# main.net
KiCad netlist of a schematic drawn in EAGLE
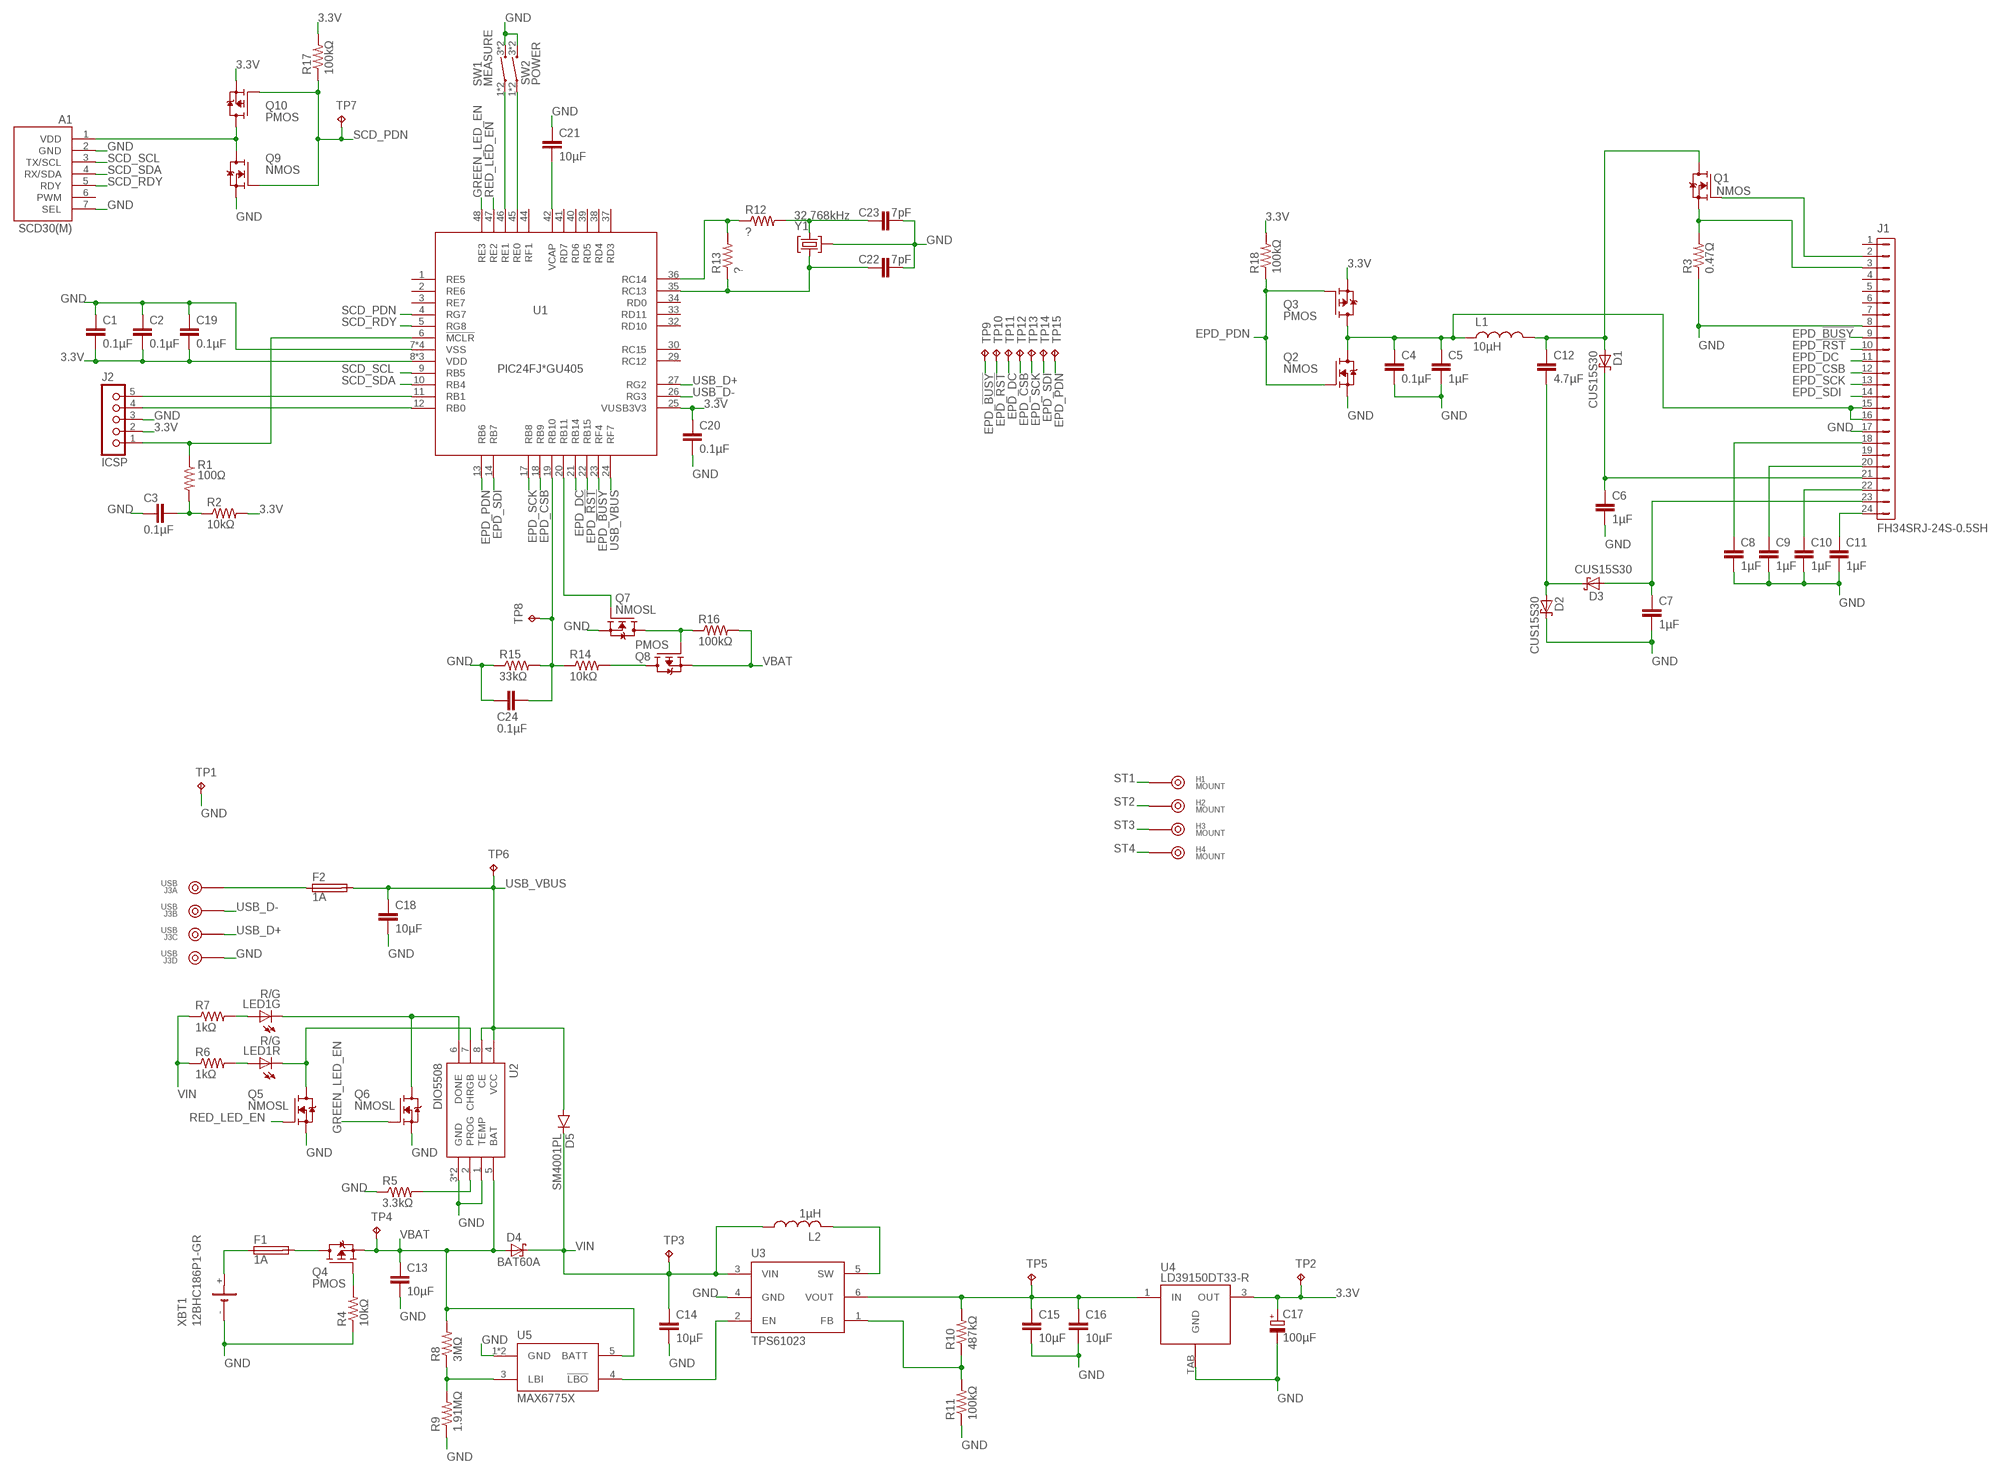
[diagram p0: schematic, sheet 1]

(export (version "E")
  (design (tool "Eeschema 10.0.6"))
  (components
    (comp (ref "A1")
      (value "SCD30(M)")
      (footprint "eagle-import:SCD30-MIRRORED")
      (libsource (lib "eagle-import") (part "SCD30(M)"))
    )
    (comp (ref "C1")
      (value "0.1µF")
      (footprint "eagle-import:C0603")
      (libsource (lib "eagle-import") (part "C-EUC0603"))
    )
    (comp (ref "C2")
      (value "0.1µF")
      (footprint "eagle-import:C0603")
      (libsource (lib "eagle-import") (part "C-EUC0603"))
    )
    (comp (ref "C3")
      (value "0.1µF")
      (footprint "eagle-import:C0603")
      (libsource (lib "eagle-import") (part "C-EUC0603"))
    )
    (comp (ref "C4")
      (value "0.1µF")
      (footprint "eagle-import:C0603")
      (libsource (lib "eagle-import") (part "C-EUC0603"))
    )
    (comp (ref "C5")
      (value "1µF")
      (footprint "eagle-import:C0603")
      (libsource (lib "eagle-import") (part "C-EUC0603"))
    )
    (comp (ref "C6")
      (value "1µF")
      (footprint "eagle-import:C0603")
      (libsource (lib "eagle-import") (part "C-EUC0603"))
    )
    (comp (ref "C7")
      (value "1µF")
      (footprint "eagle-import:C0603")
      (libsource (lib "eagle-import") (part "C-EUC0603"))
    )
    (comp (ref "C8")
      (value "1µF")
      (footprint "eagle-import:C0603")
      (libsource (lib "eagle-import") (part "C-EUC0603"))
    )
    (comp (ref "C9")
      (value "1µF")
      (footprint "eagle-import:C0603")
      (libsource (lib "eagle-import") (part "C-EUC0603"))
    )
    (comp (ref "C10")
      (value "1µF")
      (footprint "eagle-import:C0603")
      (libsource (lib "eagle-import") (part "C-EUC0603"))
    )
    (comp (ref "C11")
      (value "1µF")
      (footprint "eagle-import:C0603")
      (libsource (lib "eagle-import") (part "C-EUC0603"))
    )
    (comp (ref "C12")
      (value "4.7µF")
      (footprint "eagle-import:C0805")
      (libsource (lib "eagle-import") (part "C-EUC0805"))
    )
    (comp (ref "C13")
      (value "10µF")
      (footprint "eagle-import:C0805")
      (libsource (lib "eagle-import") (part "C-EUC0805"))
    )
    (comp (ref "C14")
      (value "10µF")
      (footprint "eagle-import:C0805")
      (libsource (lib "eagle-import") (part "C-EUC0805"))
    )
    (comp (ref "C15")
      (value "10µF")
      (footprint "eagle-import:C0805")
      (libsource (lib "eagle-import") (part "C-EUC0805"))
    )
    (comp (ref "C16")
      (value "10µF")
      (footprint "eagle-import:C0805")
      (libsource (lib "eagle-import") (part "C-EUC0805"))
    )
    (comp (ref "C17")
      (value "100µF")
      (footprint "eagle-import:PANASONIC_D")
      (libsource (lib "eagle-import") (part "CPOL-EUD"))
    )
    (comp (ref "C18")
      (value "10µF")
      (footprint "eagle-import:C0805")
      (libsource (lib "eagle-import") (part "C-EUC0805"))
    )
    (comp (ref "C19")
      (value "0.1µF")
      (footprint "eagle-import:C0603")
      (libsource (lib "eagle-import") (part "C-EUC0603"))
    )
    (comp (ref "C20")
      (value "0.1µF")
      (footprint "eagle-import:C0603")
      (libsource (lib "eagle-import") (part "C-EUC0603"))
    )
    (comp (ref "C21")
      (value "10µF")
      (footprint "eagle-import:C0805")
      (libsource (lib "eagle-import") (part "C-EUC0805"))
    )
    (comp (ref "C22")
      (value "7pF")
      (footprint "eagle-import:C0603")
      (libsource (lib "eagle-import") (part "C-EUC0603"))
    )
    (comp (ref "C23")
      (value "7pF")
      (footprint "eagle-import:C0603")
      (libsource (lib "eagle-import") (part "C-EUC0603"))
    )
    (comp (ref "C24")
      (value "0.1µF")
      (footprint "eagle-import:C0603")
      (libsource (lib "eagle-import") (part "C-EUC0603"))
    )
    (comp (ref "D1")
      (value "CUS15S30")
      (footprint "eagle-import:SOD323")
      (libsource (lib "eagle-import") (part "SOD323-SCHOTTKY"))
    )
    (comp (ref "D2")
      (value "CUS15S30")
      (footprint "eagle-import:SOD323")
      (libsource (lib "eagle-import") (part "SOD323-SCHOTTKY"))
    )
    (comp (ref "D3")
      (value "CUS15S30")
      (footprint "eagle-import:SOD323")
      (libsource (lib "eagle-import") (part "SOD323-SCHOTTKY"))
    )
    (comp (ref "D4")
      (value "BAT60A")
      (footprint "eagle-import:SOD323")
      (libsource (lib "eagle-import") (part "ExtraParts_SOD323-SCHOTTKY"))
    )
    (comp (ref "D5")
      (value "SM4001PL")
      (footprint "eagle-import:SOD123")
      (libsource (lib "eagle-import") (part "DIODE-SOD123"))
    )
    (comp (ref "F1")
      (value "1A")
      (footprint "eagle-import:C0603")
      (libsource (lib "eagle-import") (part "0603-FUSE"))
    )
    (comp (ref "F2")
      (value "1A")
      (footprint "eagle-import:C0603")
      (libsource (lib "eagle-import") (part "0603-FUSE"))
    )
    (comp (ref "H1")
      (value "MOUNT")
      (footprint "eagle-import:7466313R")
      (libsource (lib "eagle-import") (part "7466313R"))
    )
    (comp (ref "H2")
      (value "MOUNT")
      (footprint "eagle-import:7466313R")
      (libsource (lib "eagle-import") (part "7466313R"))
    )
    (comp (ref "H3")
      (value "MOUNT")
      (footprint "eagle-import:7466313R")
      (libsource (lib "eagle-import") (part "7466313R"))
    )
    (comp (ref "H4")
      (value "MOUNT")
      (footprint "eagle-import:7466313R")
      (libsource (lib "eagle-import") (part "7466313R"))
    )
    (comp (ref "J1")
      (value "FH34SRJ-24S-0.5SH")
      (footprint "eagle-import:FH34SRJ-24S-0.5SH")
      (libsource (lib "eagle-import") (part "FH34SRJ-24S-0.5SH"))
    )
    (comp (ref "J2")
      (value "ICSP")
      (footprint "eagle-import:5PIN-1.27")
      (libsource (lib "eagle-import") (part "5PIN-1.27"))
    )
    (comp (ref "J3")
      (value "USB")
      (footprint "eagle-import:4PIN")
      (libsource (lib "eagle-import") (part "GEN-4PIN"))
    )
    (comp (ref "L1")
      (value "10µH")
      (footprint "eagle-import:L3225M")
      (libsource (lib "eagle-import") (part "L-USL3225M"))
    )
    (comp (ref "L2")
      (value "1µH")
      (footprint "eagle-import:TYS4030")
      (libsource (lib "eagle-import") (part "TYS4030"))
    )
    (comp (ref "LED1")
      (value "R/G")
      (footprint "eagle-import:0805-DUALLED")
      (libsource (lib "eagle-import") (part "APHBM2012LSURKZGKC"))
    )
    (comp (ref "Q1")
      (value "NMOS")
      (footprint "eagle-import:SOT23")
      (libsource (lib "eagle-import") (part "SOT23-N-MOSFET"))
    )
    (comp (ref "Q2")
      (value "NMOS")
      (footprint "eagle-import:SOT23")
      (libsource (lib "eagle-import") (part "SOT23-N-MOSFET"))
    )
    (comp (ref "Q3")
      (value "PMOS")
      (footprint "eagle-import:SOT23")
      (libsource (lib "eagle-import") (part "SOT23-P-MOSFET"))
    )
    (comp (ref "Q4")
      (value "PMOS")
      (footprint "eagle-import:SOT23")
      (libsource (lib "eagle-import") (part "SOT23-P-MOSFET"))
    )
    (comp (ref "Q5")
      (value "NMOSL")
      (footprint "eagle-import:SOT23")
      (libsource (lib "eagle-import") (part "SOT23-N-MOSFET"))
    )
    (comp (ref "Q6")
      (value "NMOSL")
      (footprint "eagle-import:SOT23")
      (libsource (lib "eagle-import") (part "SOT23-N-MOSFET"))
    )
    (comp (ref "Q7")
      (value "NMOSL")
      (footprint "eagle-import:SOT23")
      (libsource (lib "eagle-import") (part "SOT23-N-MOSFET"))
    )
    (comp (ref "Q8")
      (value "PMOS")
      (footprint "eagle-import:SOT23")
      (libsource (lib "eagle-import") (part "SOT23-P-MOSFET"))
    )
    (comp (ref "Q9")
      (value "NMOS")
      (footprint "eagle-import:SOT23")
      (libsource (lib "eagle-import") (part "SOT23-N-MOSFET"))
    )
    (comp (ref "Q10")
      (value "PMOS")
      (footprint "eagle-import:SOT23")
      (libsource (lib "eagle-import") (part "SOT23-P-MOSFET"))
    )
    (comp (ref "R1")
      (value "100Ω")
      (footprint "eagle-import:R0603")
      (libsource (lib "eagle-import") (part "R-US_R0603"))
    )
    (comp (ref "R2")
      (value "10kΩ")
      (footprint "eagle-import:R0603")
      (libsource (lib "eagle-import") (part "R-US_R0603"))
    )
    (comp (ref "R3")
      (value "0.47Ω")
      (footprint "eagle-import:R0603")
      (libsource (lib "eagle-import") (part "R-US_R0603"))
    )
    (comp (ref "R4")
      (value "10kΩ")
      (footprint "eagle-import:R0603")
      (libsource (lib "eagle-import") (part "R-US_R0603"))
    )
    (comp (ref "R5")
      (value "3.3kΩ")
      (footprint "eagle-import:R0603")
      (libsource (lib "eagle-import") (part "R-US_R0603"))
    )
    (comp (ref "R6")
      (value "1kΩ")
      (footprint "eagle-import:R0603")
      (libsource (lib "eagle-import") (part "R-US_R0603"))
    )
    (comp (ref "R7")
      (value "1kΩ")
      (footprint "eagle-import:R0603")
      (libsource (lib "eagle-import") (part "R-US_R0603"))
    )
    (comp (ref "R8")
      (value "3MΩ")
      (footprint "eagle-import:R0603")
      (libsource (lib "eagle-import") (part "R-US_R0603"))
    )
    (comp (ref "R9")
      (value "1.91MΩ")
      (footprint "eagle-import:R0603")
      (libsource (lib "eagle-import") (part "R-US_R0603"))
    )
    (comp (ref "R10")
      (value "487kΩ")
      (footprint "eagle-import:R0603")
      (libsource (lib "eagle-import") (part "R-US_R0603"))
    )
    (comp (ref "R11")
      (value "100kΩ")
      (footprint "eagle-import:R0603")
      (libsource (lib "eagle-import") (part "R-US_R0603"))
    )
    (comp (ref "R12")
      (value "?")
      (footprint "eagle-import:R0603")
      (libsource (lib "eagle-import") (part "R-US_R0603"))
    )
    (comp (ref "R13")
      (value "?")
      (footprint "eagle-import:R0603")
      (libsource (lib "eagle-import") (part "R-US_R0603"))
    )
    (comp (ref "R14")
      (value "10kΩ")
      (footprint "eagle-import:R0603")
      (libsource (lib "eagle-import") (part "R-US_R0603"))
    )
    (comp (ref "R15")
      (value "33kΩ")
      (footprint "eagle-import:R0603")
      (libsource (lib "eagle-import") (part "R-US_R0603"))
    )
    (comp (ref "R16")
      (value "100kΩ")
      (footprint "eagle-import:R0603")
      (libsource (lib "eagle-import") (part "R-US_R0603"))
    )
    (comp (ref "R17")
      (value "100kΩ")
      (footprint "eagle-import:R0603")
      (libsource (lib "eagle-import") (part "R-US_R0603"))
    )
    (comp (ref "R18")
      (value "100kΩ")
      (footprint "eagle-import:R0603")
      (libsource (lib "eagle-import") (part "R-US_R0603"))
    )
    (comp (ref "SW1")
      (value "MEASURE")
      (footprint "eagle-import:PTS647")
      (libsource (lib "eagle-import") (part "PTS647"))
    )
    (comp (ref "SW2")
      (value "POWER")
      (footprint "eagle-import:PTS647")
      (libsource (lib "eagle-import") (part "PTS647"))
    )
    (comp (ref "TP1")
      (value "RCU-0(J)")
      (footprint "eagle-import:TP_0603_JOINED")
      (fields (field (name "TP_SIGNAL_NAME") "GND"))
      (libsource (lib "eagle-import") (part "RCU-0(J)"))
    )
    (comp (ref "TP2")
      (value "RCU-0(J)")
      (footprint "eagle-import:TP_0603_JOINED")
      (fields (field (name "TP_SIGNAL_NAME") "3.3V"))
      (libsource (lib "eagle-import") (part "RCU-0(J)"))
    )
    (comp (ref "TP3")
      (value "RCU-0(J)")
      (footprint "eagle-import:TP_0603_JOINED")
      (fields (field (name "TP_SIGNAL_NAME") "VIN"))
      (libsource (lib "eagle-import") (part "RCU-0(J)"))
    )
    (comp (ref "TP4")
      (value "RCU-0(J)")
      (footprint "eagle-import:TP_0603_JOINED")
      (fields (field (name "TP_SIGNAL_NAME") "VBAT"))
      (libsource (lib "eagle-import") (part "RCU-0(J)"))
    )
    (comp (ref "TP5")
      (value "RCU-0(J)")
      (footprint "eagle-import:TP_0603_JOINED")
      (fields (field (name "TP_SIGNAL_NAME") "VBOOST"))
      (libsource (lib "eagle-import") (part "RCU-0(J)"))
    )
    (comp (ref "TP6")
      (value "RCU-0(J)")
      (footprint "eagle-import:TP_0603_JOINED")
      (fields (field (name "TP_SIGNAL_NAME") "USB_V"))
      (libsource (lib "eagle-import") (part "RCU-0(J)"))
    )
    (comp (ref "TP7")
      (value "RCU-0(J)")
      (footprint "eagle-import:TP_0603_JOINED")
      (fields (field (name "TP_SIGNAL_NAME") "SCD_PDN"))
      (libsource (lib "eagle-import") (part "RCU-0(J)"))
    )
    (comp (ref "TP8")
      (value "RCU-0(J)")
      (footprint "eagle-import:TP_0603_JOINED")
      (fields (field (name "TP_SIGNAL_NAME") "VBAT_M"))
      (libsource (lib "eagle-import") (part "RCU-0(J)"))
    )
    (comp (ref "TP9")
      (value "RCU-0(J)")
      (footprint "eagle-import:TP_0603_JOINED")
      (fields (field (name "TP_SIGNAL_NAME") "EPD_!BUSY"))
      (libsource (lib "eagle-import") (part "RCU-0(J)"))
    )
    (comp (ref "TP10")
      (value "RCU-0(J)")
      (footprint "eagle-import:TP_0603_JOINED")
      (fields (field (name "TP_SIGNAL_NAME") "EPD_!RST"))
      (libsource (lib "eagle-import") (part "RCU-0(J)"))
    )
    (comp (ref "TP11")
      (value "RCU-0(J)")
      (footprint "eagle-import:TP_0603_JOINED")
      (fields (field (name "TP_SIGNAL_NAME") "EPD_DC"))
      (libsource (lib "eagle-import") (part "RCU-0(J)"))
    )
    (comp (ref "TP12")
      (value "RCU-0(J)")
      (footprint "eagle-import:TP_0603_JOINED")
      (fields (field (name "TP_SIGNAL_NAME") "EPD_CSB"))
      (libsource (lib "eagle-import") (part "RCU-0(J)"))
    )
    (comp (ref "TP13")
      (value "RCU-0(J)")
      (footprint "eagle-import:TP_0603_JOINED")
      (fields (field (name "TP_SIGNAL_NAME") "EPD_SCK"))
      (libsource (lib "eagle-import") (part "RCU-0(J)"))
    )
    (comp (ref "TP14")
      (value "RCU-0(J)")
      (footprint "eagle-import:TP_0603_JOINED")
      (fields (field (name "TP_SIGNAL_NAME") "EPD_SDI"))
      (libsource (lib "eagle-import") (part "RCU-0(J)"))
    )
    (comp (ref "TP15")
      (value "RCU-0(J)")
      (footprint "eagle-import:TP_0603_JOINED")
      (fields (field (name "TP_SIGNAL_NAME") "EPD_PDN"))
      (libsource (lib "eagle-import") (part "RCU-0(J)"))
    )
    (comp (ref "U1")
      (value "PIC24FJ*GU405")
      (footprint "eagle-import:TQFP48")
      (libsource (lib "eagle-import") (part "PIC24FJGU405"))
    )
    (comp (ref "U2")
      (value "DIO5508")
      (footprint "eagle-import:SOIC8-EP")
      (libsource (lib "eagle-import") (part "DIO5508"))
    )
    (comp (ref "U3")
      (value "TPS61023")
      (footprint "eagle-import:SOT563")
      (libsource (lib "eagle-import") (part "TPS61023"))
    )
    (comp (ref "U4")
      (value "LD39150DT33-R")
      (footprint "eagle-import:DPAK")
      (libsource (lib "eagle-import") (part "DPAK-LDO"))
    )
    (comp (ref "U5")
      (value "MAX6775X")
      (footprint "eagle-import:SC70-5")
      (libsource (lib "eagle-import") (part "MAX6776X"))
    )
    (comp (ref "XBT1")
      (value "12BHC186P1-GR")
      (footprint "eagle-import:12BHC186P1-GR")
      (libsource (lib "eagle-import") (part "12BHC186P1-GR"))
    )
    (comp (ref "Y1")
      (value "32.768kHz")
      (footprint "eagle-import:MS1V-T1K")
      (libsource (lib "eagle-import") (part "MS1V-T1K"))
    )
  )
  (nets
    (net (code "1") (name "/3.3V") (class "Default")
      (node (ref "C1") (pin "2") (pinfunction "2_2") (pintype "passive"))
      (node (ref "C17") (pin "+") (pinfunction "+_+") (pintype "passive"))
      (node (ref "C19") (pin "2") (pinfunction "2_2") (pintype "passive"))
      (node (ref "C2") (pin "2") (pinfunction "2_2") (pintype "passive"))
      (node (ref "C20") (pin "1") (pinfunction "1_1") (pintype "passive"))
      (node (ref "J2") (pin "2") (pinfunction "2_2") (pintype "passive"))
      (node (ref "Q10") (pin "2") (pinfunction "S_2") (pintype "passive"))
      (node (ref "Q3") (pin "2") (pinfunction "S_2") (pintype "passive"))
      (node (ref "R17") (pin "2") (pinfunction "2_2") (pintype "passive"))
      (node (ref "R18") (pin "2") (pinfunction "2_2") (pintype "passive"))
      (node (ref "R2") (pin "2") (pinfunction "2_2") (pintype "passive"))
      (node (ref "TP2") (pin "1") (pinfunction "TP_1") (pintype "input"))
      (node (ref "U1") (pin "15") (pinfunction "VDD_15") (pintype "bidirectional"))
      (node (ref "U1") (pin "25") (pinfunction "VUSB3V3_25") (pintype "bidirectional"))
      (node (ref "U1") (pin "28") (pinfunction "VDD_28") (pintype "bidirectional"))
      (node (ref "U1") (pin "8") (pinfunction "VDD_8") (pintype "bidirectional"))
      (node (ref "U4") (pin "3") (pinfunction "OUT_3") (pintype "bidirectional"))
    )
    (net (code "2") (name "/EPD_CSB") (class "Default")
      (node (ref "J1") (pin "12") (pinfunction "12_12") (pintype "passive"))
      (node (ref "TP12") (pin "1") (pinfunction "TP_1") (pintype "input"))
      (node (ref "U1") (pin "18") (pinfunction "RB9_18") (pintype "bidirectional"))
    )
    (net (code "3") (name "/EPD_DC") (class "Default")
      (node (ref "J1") (pin "11") (pinfunction "11_11") (pintype "passive"))
      (node (ref "TP11") (pin "1") (pinfunction "TP_1") (pintype "input"))
      (node (ref "U1") (pin "21") (pinfunction "RB14_21") (pintype "bidirectional"))
    )
    (net (code "4") (name "/EPD_PDN") (class "Default")
      (node (ref "Q2") (pin "1") (pinfunction "G_1") (pintype "passive"))
      (node (ref "Q3") (pin "1") (pinfunction "G_1") (pintype "passive"))
      (node (ref "R18") (pin "1") (pinfunction "1_1") (pintype "passive"))
      (node (ref "TP15") (pin "1") (pinfunction "TP_1") (pintype "input"))
      (node (ref "U1") (pin "13") (pinfunction "RB6_13") (pintype "bidirectional"))
    )
    (net (code "5") (name "/EPD_SCK") (class "Default")
      (node (ref "J1") (pin "13") (pinfunction "13_13") (pintype "passive"))
      (node (ref "TP13") (pin "1") (pinfunction "TP_1") (pintype "input"))
      (node (ref "U1") (pin "17") (pinfunction "RB8_17") (pintype "bidirectional"))
    )
    (net (code "6") (name "/EPD_SDI") (class "Default")
      (node (ref "J1") (pin "14") (pinfunction "14_14") (pintype "passive"))
      (node (ref "TP14") (pin "1") (pinfunction "TP_1") (pintype "input"))
      (node (ref "U1") (pin "14") (pinfunction "RB7_14") (pintype "bidirectional"))
    )
    (net (code "7") (name "/EPD_~{BUSY}") (class "Default")
      (node (ref "J1") (pin "9") (pinfunction "9_9") (pintype "passive"))
      (node (ref "TP9") (pin "1") (pinfunction "TP_1") (pintype "input"))
      (node (ref "U1") (pin "23") (pinfunction "RF4_23") (pintype "bidirectional"))
    )
    (net (code "8") (name "/EPD_~{RST}") (class "Default")
      (node (ref "J1") (pin "10") (pinfunction "10_10") (pintype "passive"))
      (node (ref "TP10") (pin "1") (pinfunction "TP_1") (pintype "input"))
      (node (ref "U1") (pin "22") (pinfunction "RB15_22") (pintype "bidirectional"))
    )
    (net (code "9") (name "/GND") (class "Default")
      (node (ref "A1") (pin "2") (pinfunction "GND_2") (pintype "bidirectional"))
      (node (ref "A1") (pin "7") (pinfunction "SEL_7") (pintype "bidirectional"))
      (node (ref "C1") (pin "1") (pinfunction "1_1") (pintype "passive"))
      (node (ref "C10") (pin "2") (pinfunction "2_2") (pintype "passive"))
      (node (ref "C11") (pin "2") (pinfunction "2_2") (pintype "passive"))
      (node (ref "C13") (pin "2") (pinfunction "2_2") (pintype "passive"))
      (node (ref "C14") (pin "2") (pinfunction "2_2") (pintype "passive"))
      (node (ref "C15") (pin "2") (pinfunction "2_2") (pintype "passive"))
      (node (ref "C16") (pin "2") (pinfunction "2_2") (pintype "passive"))
      (node (ref "C17") (pin "-") (pinfunction "-_-") (pintype "passive"))
      (node (ref "C18") (pin "2") (pinfunction "2_2") (pintype "passive"))
      (node (ref "C19") (pin "1") (pinfunction "1_1") (pintype "passive"))
      (node (ref "C2") (pin "1") (pinfunction "1_1") (pintype "passive"))
      (node (ref "C20") (pin "2") (pinfunction "2_2") (pintype "passive"))
      (node (ref "C21") (pin "1") (pinfunction "1_1") (pintype "passive"))
      (node (ref "C22") (pin "2") (pinfunction "2_2") (pintype "passive"))
      (node (ref "C23") (pin "2") (pinfunction "2_2") (pintype "passive"))
      (node (ref "C24") (pin "2") (pinfunction "2_2") (pintype "passive"))
      (node (ref "C3") (pin "2") (pinfunction "2_2") (pintype "passive"))
      (node (ref "C4") (pin "2") (pinfunction "2_2") (pintype "passive"))
      (node (ref "C5") (pin "2") (pinfunction "2_2") (pintype "passive"))
      (node (ref "C6") (pin "2") (pinfunction "2_2") (pintype "passive"))
      (node (ref "C7") (pin "2") (pinfunction "2_2") (pintype "passive"))
      (node (ref "C8") (pin "2") (pinfunction "2_2") (pintype "passive"))
      (node (ref "C9") (pin "2") (pinfunction "2_2") (pintype "passive"))
      (node (ref "D2") (pin "1") (pinfunction "C_1") (pintype "passive"))
      (node (ref "J1") (pin "17") (pinfunction "17_17") (pintype "passive"))
      (node (ref "J1") (pin "8") (pinfunction "8_8") (pintype "passive"))
      (node (ref "J2") (pin "3") (pinfunction "3_3") (pintype "passive"))
      (node (ref "J3") (pin "4") (pinfunction "P$1_4") (pintype "bidirectional"))
      (node (ref "Q2") (pin "2") (pinfunction "S_2") (pintype "passive"))
      (node (ref "Q5") (pin "2") (pinfunction "S_2") (pintype "passive"))
      (node (ref "Q6") (pin "2") (pinfunction "S_2") (pintype "passive"))
      (node (ref "Q7") (pin "2") (pinfunction "S_2") (pintype "passive"))
      (node (ref "Q9") (pin "2") (pinfunction "S_2") (pintype "passive"))
      (node (ref "R11") (pin "1") (pinfunction "1_1") (pintype "passive"))
      (node (ref "R15") (pin "1") (pinfunction "1_1") (pintype "passive"))
      (node (ref "R3") (pin "1") (pinfunction "1_1") (pintype "passive"))
      (node (ref "R4") (pin "1") (pinfunction "1_1") (pintype "passive"))
      (node (ref "R5") (pin "1") (pinfunction "1_1") (pintype "passive"))
      (node (ref "R9") (pin "1") (pinfunction "1_1") (pintype "passive"))
      (node (ref "SW1") (pin "3") (pinfunction "2_3") (pintype "passive"))
      (node (ref "SW1") (pin "4") (pinfunction "2_4") (pintype "passive"))
      (node (ref "SW2") (pin "3") (pinfunction "2_3") (pintype "passive"))
      (node (ref "SW2") (pin "4") (pinfunction "2_4") (pintype "passive"))
      (node (ref "TP1") (pin "1") (pinfunction "TP_1") (pintype "input"))
      (node (ref "U1") (pin "16") (pinfunction "VSS_16") (pintype "bidirectional"))
      (node (ref "U1") (pin "31") (pinfunction "VSS_31") (pintype "bidirectional"))
      (node (ref "U1") (pin "43") (pinfunction "VSS_43") (pintype "bidirectional"))
      (node (ref "U1") (pin "7") (pinfunction "VSS_7") (pintype "bidirectional"))
      (node (ref "U2") (pin "1") (pinfunction "TEMP_1") (pintype "bidirectional"))
      (node (ref "U2") (pin "3") (pinfunction "GND_3") (pintype "bidirectional"))
      (node (ref "U2") (pin "EP") (pinfunction "GND_EP") (pintype "bidirectional"))
      (node (ref "U3") (pin "4") (pinfunction "GND_4") (pintype "bidirectional"))
      (node (ref "U4") (pin "TAB") (pinfunction "GND_TAB") (pintype "bidirectional"))
      (node (ref "U5") (pin "1") (pinfunction "GND_1") (pintype "power_in"))
      (node (ref "U5") (pin "2") (pinfunction "GND_2") (pintype "power_in"))
      (node (ref "XBT1") (pin "-") (pinfunction "-_-") (pintype "passive"))
      (node (ref "Y1") (pin "GND") (pinfunction "3_GND") (pintype "passive"))
    )
    (net (code "10") (name "/GREEN_LED_EN") (class "Default")
      (node (ref "Q6") (pin "1") (pinfunction "G_1") (pintype "passive"))
      (node (ref "U1") (pin "48") (pinfunction "RE3_48") (pintype "bidirectional"))
    )
    (net (code "11") (name "/RED_LED_EN") (class "Default")
      (node (ref "Q5") (pin "1") (pinfunction "G_1") (pintype "passive"))
      (node (ref "U1") (pin "47") (pinfunction "RE2_47") (pintype "bidirectional"))
    )
    (net (code "12") (name "/SCD_PDN") (class "Default")
      (node (ref "Q10") (pin "1") (pinfunction "G_1") (pintype "passive"))
      (node (ref "Q9") (pin "1") (pinfunction "G_1") (pintype "passive"))
      (node (ref "R17") (pin "1") (pinfunction "1_1") (pintype "passive"))
      (node (ref "TP7") (pin "1") (pinfunction "TP_1") (pintype "input"))
      (node (ref "U1") (pin "4") (pinfunction "RG7_4") (pintype "bidirectional"))
    )
    (net (code "13") (name "/SCD_RDY") (class "Default")
      (node (ref "A1") (pin "5") (pinfunction "RDY_5") (pintype "bidirectional"))
      (node (ref "U1") (pin "5") (pinfunction "RG8_5") (pintype "bidirectional"))
    )
    (net (code "14") (name "/SCD_SCL") (class "Default")
      (node (ref "A1") (pin "3") (pinfunction "TX/SCL_3") (pintype "bidirectional"))
      (node (ref "U1") (pin "9") (pinfunction "RB5_9") (pintype "bidirectional"))
    )
    (net (code "15") (name "/SCD_SDA") (class "Default")
      (node (ref "A1") (pin "4") (pinfunction "RX/SDA_4") (pintype "bidirectional"))
      (node (ref "U1") (pin "10") (pinfunction "RB4_10") (pintype "bidirectional"))
    )
    (net (code "16") (name "/ST1") (class "Default")
      (node (ref "H1") (pin "H1") (pinfunction "P$1_H1") (pintype "bidirectional"))
      (node (ref "H1") (pin "H2") (pinfunction "P$1_H2") (pintype "bidirectional"))
      (node (ref "H1") (pin "P") (pinfunction "P$1_P") (pintype "bidirectional"))
    )
    (net (code "17") (name "/ST2") (class "Default")
      (node (ref "H2") (pin "H1") (pinfunction "P$1_H1") (pintype "bidirectional"))
      (node (ref "H2") (pin "H2") (pinfunction "P$1_H2") (pintype "bidirectional"))
      (node (ref "H2") (pin "P") (pinfunction "P$1_P") (pintype "bidirectional"))
    )
    (net (code "18") (name "/ST3") (class "Default")
      (node (ref "H3") (pin "H1") (pinfunction "P$1_H1") (pintype "bidirectional"))
      (node (ref "H3") (pin "H2") (pinfunction "P$1_H2") (pintype "bidirectional"))
      (node (ref "H3") (pin "P") (pinfunction "P$1_P") (pintype "bidirectional"))
    )
    (net (code "19") (name "/ST4") (class "Default")
      (node (ref "H4") (pin "H1") (pinfunction "P$1_H1") (pintype "bidirectional"))
      (node (ref "H4") (pin "H2") (pinfunction "P$1_H2") (pintype "bidirectional"))
      (node (ref "H4") (pin "P") (pinfunction "P$1_P") (pintype "bidirectional"))
    )
    (net (code "20") (name "/USB_D+") (class "Default")
      (node (ref "J3") (pin "3") (pinfunction "P$1_3") (pintype "bidirectional"))
      (node (ref "U1") (pin "27") (pinfunction "RG2_27") (pintype "bidirectional"))
    )
    (net (code "21") (name "/USB_D-") (class "Default")
      (node (ref "J3") (pin "2") (pinfunction "P$1_2") (pintype "bidirectional"))
      (node (ref "U1") (pin "26") (pinfunction "RG3_26") (pintype "bidirectional"))
    )
    (net (code "22") (name "/USB_VBUS") (class "Default")
      (node (ref "C18") (pin "1") (pinfunction "1_1") (pintype "passive"))
      (node (ref "D5") (pin "A") (pinfunction "A_A") (pintype "passive"))
      (node (ref "F2") (pin "2") (pinfunction "2_2") (pintype "passive"))
      (node (ref "TP6") (pin "1") (pinfunction "TP_1") (pintype "input"))
      (node (ref "U1") (pin "24") (pinfunction "RF7_24") (pintype "bidirectional"))
      (node (ref "U2") (pin "4") (pinfunction "VCC_4") (pintype "bidirectional"))
      (node (ref "U2") (pin "8") (pinfunction "CE_8") (pintype "bidirectional"))
    )
    (net (code "23") (name "/VBAT") (class "Default")
      (node (ref "C13") (pin "1") (pinfunction "1_1") (pintype "passive"))
      (node (ref "D4") (pin "2") (pinfunction "A_2") (pintype "passive"))
      (node (ref "Q4") (pin "2") (pinfunction "S_2") (pintype "passive"))
      (node (ref "Q8") (pin "2") (pinfunction "S_2") (pintype "passive"))
      (node (ref "R16") (pin "2") (pinfunction "2_2") (pintype "passive"))
      (node (ref "R8") (pin "2") (pinfunction "2_2") (pintype "passive"))
      (node (ref "TP4") (pin "1") (pinfunction "TP_1") (pintype "input"))
      (node (ref "U2") (pin "5") (pinfunction "BAT_5") (pintype "bidirectional"))
      (node (ref "U5") (pin "5") (pinfunction "BATT_5") (pintype "power_in"))
    )
    (net (code "24") (name "/VIN") (class "Default")
      (node (ref "C14") (pin "1") (pinfunction "1_1") (pintype "passive"))
      (node (ref "D4") (pin "1") (pinfunction "C_1") (pintype "passive"))
      (node (ref "D5") (pin "C") (pinfunction "C_C") (pintype "passive"))
      (node (ref "L2") (pin "1") (pinfunction "1_1") (pintype "passive"))
      (node (ref "R6") (pin "1") (pinfunction "1_1") (pintype "passive"))
      (node (ref "R7") (pin "1") (pinfunction "1_1") (pintype "passive"))
      (node (ref "TP3") (pin "1") (pinfunction "TP_1") (pintype "input"))
      (node (ref "U3") (pin "3") (pinfunction "VIN_3") (pintype "bidirectional"))
    )
    (net (code "25") (name "Net-(A1-VDD)") (class "Default")
      (node (ref "A1") (pin "1") (pinfunction "VDD_1") (pintype "bidirectional"))
      (node (ref "Q10") (pin "3") (pinfunction "D_3") (pintype "passive"))
      (node (ref "Q9") (pin "3") (pinfunction "D_3") (pintype "passive"))
    )
    (net (code "26") (name "Net-(C3-Pad1)") (class "Default")
      (node (ref "C3") (pin "1") (pinfunction "1_1") (pintype "passive"))
      (node (ref "R1") (pin "2") (pinfunction "2_2") (pintype "passive"))
      (node (ref "R2") (pin "1") (pinfunction "1_1") (pintype "passive"))
    )
    (net (code "27") (name "Net-(C8-Pad1)") (class "Default")
      (node (ref "C8") (pin "1") (pinfunction "1_1") (pintype "passive"))
      (node (ref "J1") (pin "18") (pinfunction "18_18") (pintype "passive"))
    )
    (net (code "28") (name "Net-(C9-Pad1)") (class "Default")
      (node (ref "C9") (pin "1") (pinfunction "1_1") (pintype "passive"))
      (node (ref "J1") (pin "20") (pinfunction "20_20") (pintype "passive"))
    )
    (net (code "29") (name "Net-(C10-Pad1)") (class "Default")
      (node (ref "C10") (pin "1") (pinfunction "1_1") (pintype "passive"))
      (node (ref "J1") (pin "22") (pinfunction "22_22") (pintype "passive"))
    )
    (net (code "30") (name "Net-(C11-Pad1)") (class "Default")
      (node (ref "C11") (pin "1") (pinfunction "1_1") (pintype "passive"))
      (node (ref "J1") (pin "24") (pinfunction "24_24") (pintype "passive"))
    )
    (net (code "31") (name "Net-(C23-Pad1)") (class "Default")
      (node (ref "C23") (pin "1") (pinfunction "1_1") (pintype "passive"))
      (node (ref "R12") (pin "2") (pinfunction "2_2") (pintype "passive"))
      (node (ref "Y1") (pin "1") (pinfunction "1_1") (pintype "passive"))
    )
    (net (code "32") (name "Net-(D1-A)") (class "Default")
      (node (ref "C12") (pin "1") (pinfunction "1_1") (pintype "passive"))
      (node (ref "D1") (pin "2") (pinfunction "A_2") (pintype "passive"))
      (node (ref "L1") (pin "2") (pinfunction "2_2") (pintype "passive"))
      (node (ref "Q1") (pin "3") (pinfunction "D_3") (pintype "passive"))
    )
    (net (code "33") (name "Net-(D1-C)") (class "Default")
      (node (ref "C6") (pin "1") (pinfunction "1_1") (pintype "passive"))
      (node (ref "D1") (pin "1") (pinfunction "C_1") (pintype "passive"))
      (node (ref "J1") (pin "21") (pinfunction "21_21") (pintype "passive"))
    )
    (net (code "34") (name "Net-(D2-A)") (class "Default")
      (node (ref "C12") (pin "2") (pinfunction "2_2") (pintype "passive"))
      (node (ref "D2") (pin "2") (pinfunction "A_2") (pintype "passive"))
      (node (ref "D3") (pin "1") (pinfunction "C_1") (pintype "passive"))
    )
    (net (code "35") (name "Net-(D3-A)") (class "Default")
      (node (ref "C7") (pin "1") (pinfunction "1_1") (pintype "passive"))
      (node (ref "D3") (pin "2") (pinfunction "A_2") (pintype "passive"))
      (node (ref "J1") (pin "23") (pinfunction "23_23") (pintype "passive"))
    )
    (net (code "36") (name "Net-(F1-Pad1)") (class "Default")
      (node (ref "F1") (pin "1") (pinfunction "1_1") (pintype "passive"))
      (node (ref "XBT1") (pin "+") (pinfunction "+_+") (pintype "passive"))
    )
    (net (code "37") (name "Net-(J3A-P$1)") (class "Default")
      (node (ref "F2") (pin "1") (pinfunction "1_1") (pintype "passive"))
      (node (ref "J3") (pin "1") (pinfunction "P$1_1") (pintype "bidirectional"))
    )
    (net (code "38") (name "Net-(LED1A-A)") (class "Default")
      (node (ref "LED1") (pin "A2") (pinfunction "A_A2") (pintype "passive"))
      (node (ref "R7") (pin "2") (pinfunction "2_2") (pintype "passive"))
    )
    (net (code "39") (name "Net-(LED1A-C)") (class "Default")
      (node (ref "LED1") (pin "K2") (pinfunction "C_K2") (pintype "passive"))
      (node (ref "Q6") (pin "3") (pinfunction "D_3") (pintype "passive"))
      (node (ref "U2") (pin "6") (pinfunction "DONE_6") (pintype "bidirectional"))
    )
    (net (code "40") (name "Net-(LED1B-A)") (class "Default")
      (node (ref "LED1") (pin "A1") (pinfunction "A_A1") (pintype "passive"))
      (node (ref "R6") (pin "2") (pinfunction "2_2") (pintype "passive"))
    )
    (net (code "41") (name "Net-(LED1B-C)") (class "Default")
      (node (ref "LED1") (pin "K1") (pinfunction "C_K1") (pintype "passive"))
      (node (ref "Q5") (pin "3") (pinfunction "D_3") (pintype "passive"))
      (node (ref "U2") (pin "7") (pinfunction "CHRGB_7") (pintype "bidirectional"))
    )
    (net (code "42") (name "Net-(Q1-G)") (class "Default")
      (node (ref "J1") (pin "2") (pinfunction "2_2") (pintype "passive"))
      (node (ref "Q1") (pin "1") (pinfunction "G_1") (pintype "passive"))
    )
    (net (code "43") (name "Net-(Q1-S)") (class "Default")
      (node (ref "J1") (pin "3") (pinfunction "3_3") (pintype "passive"))
      (node (ref "Q1") (pin "2") (pinfunction "S_2") (pintype "passive"))
      (node (ref "R3") (pin "2") (pinfunction "2_2") (pintype "passive"))
    )
    (net (code "44") (name "Net-(Q2-D)") (class "Default")
      (node (ref "C4") (pin "1") (pinfunction "1_1") (pintype "passive"))
      (node (ref "C5") (pin "1") (pinfunction "1_1") (pintype "passive"))
      (node (ref "J1") (pin "15") (pinfunction "15_15") (pintype "passive"))
      (node (ref "J1") (pin "16") (pinfunction "16_16") (pintype "passive"))
      (node (ref "L1") (pin "1") (pinfunction "1_1") (pintype "passive"))
      (node (ref "Q2") (pin "3") (pinfunction "D_3") (pintype "passive"))
      (node (ref "Q3") (pin "3") (pinfunction "D_3") (pintype "passive"))
    )
    (net (code "45") (name "Net-(Q4-D)") (class "Default")
      (node (ref "F1") (pin "2") (pinfunction "2_2") (pintype "passive"))
      (node (ref "Q4") (pin "3") (pinfunction "D_3") (pintype "passive"))
    )
    (net (code "46") (name "Net-(Q4-G)") (class "Default")
      (node (ref "Q4") (pin "1") (pinfunction "G_1") (pintype "passive"))
      (node (ref "R4") (pin "2") (pinfunction "2_2") (pintype "passive"))
    )
    (net (code "47") (name "Net-(Q7-D)") (class "Default")
      (node (ref "Q7") (pin "3") (pinfunction "D_3") (pintype "passive"))
      (node (ref "Q8") (pin "1") (pinfunction "G_1") (pintype "passive"))
      (node (ref "R16") (pin "1") (pinfunction "1_1") (pintype "passive"))
    )
    (net (code "48") (name "Net-(Q7-G)") (class "Default")
      (node (ref "Q7") (pin "1") (pinfunction "G_1") (pintype "passive"))
      (node (ref "U1") (pin "20") (pinfunction "RB11_20") (pintype "bidirectional"))
    )
    (net (code "49") (name "Net-(Q8-D)") (class "Default")
      (node (ref "Q8") (pin "3") (pinfunction "D_3") (pintype "passive"))
      (node (ref "R14") (pin "2") (pinfunction "2_2") (pintype "passive"))
    )
    (net (code "50") (name "Net-(TP5-TP)") (class "Default")
      (node (ref "C15") (pin "1") (pinfunction "1_1") (pintype "passive"))
      (node (ref "C16") (pin "1") (pinfunction "1_1") (pintype "passive"))
      (node (ref "R10") (pin "2") (pinfunction "2_2") (pintype "passive"))
      (node (ref "TP5") (pin "1") (pinfunction "TP_1") (pintype "input"))
      (node (ref "U3") (pin "6") (pinfunction "VOUT_6") (pintype "bidirectional"))
      (node (ref "U4") (pin "1") (pinfunction "IN_1") (pintype "bidirectional"))
    )
    (net (code "51") (name "Net-(TP8-TP)") (class "Default")
      (node (ref "C24") (pin "1") (pinfunction "1_1") (pintype "passive"))
      (node (ref "R14") (pin "1") (pinfunction "1_1") (pintype "passive"))
      (node (ref "R15") (pin "2") (pinfunction "2_2") (pintype "passive"))
      (node (ref "TP8") (pin "1") (pinfunction "TP_1") (pintype "input"))
      (node (ref "U1") (pin "19") (pinfunction "RB10_19") (pintype "bidirectional"))
    )
    (net (code "52") (name "Net-(U1-RB0)") (class "Default")
      (node (ref "J2") (pin "4") (pinfunction "4_4") (pintype "passive"))
      (node (ref "U1") (pin "12") (pinfunction "RB0_12") (pintype "bidirectional"))
    )
    (net (code "53") (name "Net-(U1-RB1)") (class "Default")
      (node (ref "J2") (pin "5") (pinfunction "5_5") (pintype "passive"))
      (node (ref "U1") (pin "11") (pinfunction "RB1_11") (pintype "bidirectional"))
    )
    (net (code "54") (name "Net-(U1-RC13)") (class "Default")
      (node (ref "C22") (pin "1") (pinfunction "1_1") (pintype "passive"))
      (node (ref "R13") (pin "1") (pinfunction "1_1") (pintype "passive"))
      (node (ref "U1") (pin "35") (pinfunction "RC13_35") (pintype "bidirectional"))
      (node (ref "Y1") (pin "2") (pinfunction "2_2") (pintype "passive"))
    )
    (net (code "55") (name "Net-(U1-RC14)") (class "Default")
      (node (ref "R12") (pin "1") (pinfunction "1_1") (pintype "passive"))
      (node (ref "R13") (pin "2") (pinfunction "2_2") (pintype "passive"))
      (node (ref "U1") (pin "36") (pinfunction "RC14_36") (pintype "bidirectional"))
    )
    (net (code "56") (name "Net-(U1-RE0)") (class "Default")
      (node (ref "SW2") (pin "1") (pinfunction "1_1") (pintype "passive"))
      (node (ref "SW2") (pin "2") (pinfunction "1_2") (pintype "passive"))
      (node (ref "U1") (pin "45") (pinfunction "RE0_45") (pintype "bidirectional"))
    )
    (net (code "57") (name "Net-(U1-RE1)") (class "Default")
      (node (ref "SW1") (pin "1") (pinfunction "1_1") (pintype "passive"))
      (node (ref "SW1") (pin "2") (pinfunction "1_2") (pintype "passive"))
      (node (ref "U1") (pin "46") (pinfunction "RE1_46") (pintype "bidirectional"))
    )
    (net (code "58") (name "Net-(U1-VCAP)") (class "Default")
      (node (ref "C21") (pin "2") (pinfunction "2_2") (pintype "passive"))
      (node (ref "U1") (pin "42") (pinfunction "VCAP_42") (pintype "bidirectional"))
    )
    (net (code "59") (name "Net-(U1-~{MCLR})") (class "Default")
      (node (ref "J2") (pin "1") (pinfunction "1_1") (pintype "passive"))
      (node (ref "R1") (pin "1") (pinfunction "1_1") (pintype "passive"))
      (node (ref "U1") (pin "6") (pinfunction "~{MCLR}_6") (pintype "bidirectional"))
    )
    (net (code "60") (name "Net-(U2-PROG)") (class "Default")
      (node (ref "R5") (pin "2") (pinfunction "2_2") (pintype "passive"))
      (node (ref "U2") (pin "2") (pinfunction "PROG_2") (pintype "bidirectional"))
    )
    (net (code "61") (name "Net-(U3-EN)") (class "Default")
      (node (ref "U3") (pin "2") (pinfunction "EN_2") (pintype "bidirectional"))
      (node (ref "U5") (pin "4") (pinfunction "~{LBO}_4") (pintype "bidirectional"))
    )
    (net (code "62") (name "Net-(U3-FB)") (class "Default")
      (node (ref "R10") (pin "1") (pinfunction "1_1") (pintype "passive"))
      (node (ref "R11") (pin "2") (pinfunction "2_2") (pintype "passive"))
      (node (ref "U3") (pin "1") (pinfunction "FB_1") (pintype "bidirectional"))
    )
    (net (code "63") (name "Net-(U3-SW)") (class "Default")
      (node (ref "L2") (pin "2") (pinfunction "2_2") (pintype "passive"))
      (node (ref "U3") (pin "5") (pinfunction "SW_5") (pintype "bidirectional"))
    )
    (net (code "64") (name "Net-(U5-LBI)") (class "Default")
      (node (ref "R8") (pin "1") (pinfunction "1_1") (pintype "passive"))
      (node (ref "R9") (pin "2") (pinfunction "2_2") (pintype "passive"))
      (node (ref "U5") (pin "3") (pinfunction "LBI_3") (pintype "bidirectional"))
    )
    (net (code "65") (name "unconnected-(A1-PWM-Pad6)") (class "Default")
      (node (ref "A1") (pin "6") (pinfunction "PWM_6") (pintype "bidirectional"))
    )
    (net (code "66") (name "unconnected-(J1-Pad1)") (class "Default")
      (node (ref "J1") (pin "1") (pinfunction "1_1") (pintype "passive"))
    )
    (net (code "67") (name "unconnected-(J1-Pad4)") (class "Default")
      (node (ref "J1") (pin "4") (pinfunction "4_4") (pintype "passive"))
    )
    (net (code "68") (name "unconnected-(J1-Pad5)") (class "Default")
      (node (ref "J1") (pin "5") (pinfunction "5_5") (pintype "passive"))
    )
    (net (code "69") (name "unconnected-(J1-Pad6)") (class "Default")
      (node (ref "J1") (pin "6") (pinfunction "6_6") (pintype "passive"))
    )
    (net (code "70") (name "unconnected-(J1-Pad7)") (class "Default")
      (node (ref "J1") (pin "7") (pinfunction "7_7") (pintype "passive"))
    )
    (net (code "71") (name "unconnected-(J1-Pad19)") (class "Default")
      (node (ref "J1") (pin "19") (pinfunction "19_19") (pintype "passive"))
    )
    (net (code "72") (name "unconnected-(U1-RC12-Pad29)") (class "Default")
      (node (ref "U1") (pin "29") (pinfunction "RC12_29") (pintype "bidirectional"))
    )
    (net (code "73") (name "unconnected-(U1-RC15-Pad30)") (class "Default")
      (node (ref "U1") (pin "30") (pinfunction "RC15_30") (pintype "bidirectional"))
    )
    (net (code "74") (name "unconnected-(U1-RD0-Pad34)") (class "Default")
      (node (ref "U1") (pin "34") (pinfunction "RD0_34") (pintype "bidirectional"))
    )
    (net (code "75") (name "unconnected-(U1-RD3-Pad37)") (class "Default")
      (node (ref "U1") (pin "37") (pinfunction "RD3_37") (pintype "bidirectional"))
    )
    (net (code "76") (name "unconnected-(U1-RD4-Pad38)") (class "Default")
      (node (ref "U1") (pin "38") (pinfunction "RD4_38") (pintype "bidirectional"))
    )
    (net (code "77") (name "unconnected-(U1-RD5-Pad39)") (class "Default")
      (node (ref "U1") (pin "39") (pinfunction "RD5_39") (pintype "bidirectional"))
    )
    (net (code "78") (name "unconnected-(U1-RD6-Pad40)") (class "Default")
      (node (ref "U1") (pin "40") (pinfunction "RD6_40") (pintype "bidirectional"))
    )
    (net (code "79") (name "unconnected-(U1-RD7-Pad41)") (class "Default")
      (node (ref "U1") (pin "41") (pinfunction "RD7_41") (pintype "bidirectional"))
    )
    (net (code "80") (name "unconnected-(U1-RD10-Pad32)") (class "Default")
      (node (ref "U1") (pin "32") (pinfunction "RD10_32") (pintype "bidirectional"))
    )
    (net (code "81") (name "unconnected-(U1-RD11-Pad33)") (class "Default")
      (node (ref "U1") (pin "33") (pinfunction "RD11_33") (pintype "bidirectional"))
    )
    (net (code "82") (name "unconnected-(U1-RE5-Pad1)") (class "Default")
      (node (ref "U1") (pin "1") (pinfunction "RE5_1") (pintype "bidirectional"))
    )
    (net (code "83") (name "unconnected-(U1-RE6-Pad2)") (class "Default")
      (node (ref "U1") (pin "2") (pinfunction "RE6_2") (pintype "bidirectional"))
    )
    (net (code "84") (name "unconnected-(U1-RE7-Pad3)") (class "Default")
      (node (ref "U1") (pin "3") (pinfunction "RE7_3") (pintype "bidirectional"))
    )
    (net (code "85") (name "unconnected-(U1-RF1-Pad44)") (class "Default")
      (node (ref "U1") (pin "44") (pinfunction "RF1_44") (pintype "bidirectional"))
    )
  )
)
